# ESPNTPServer.net
KiCad netlist of a schematic drawn in EAGLE
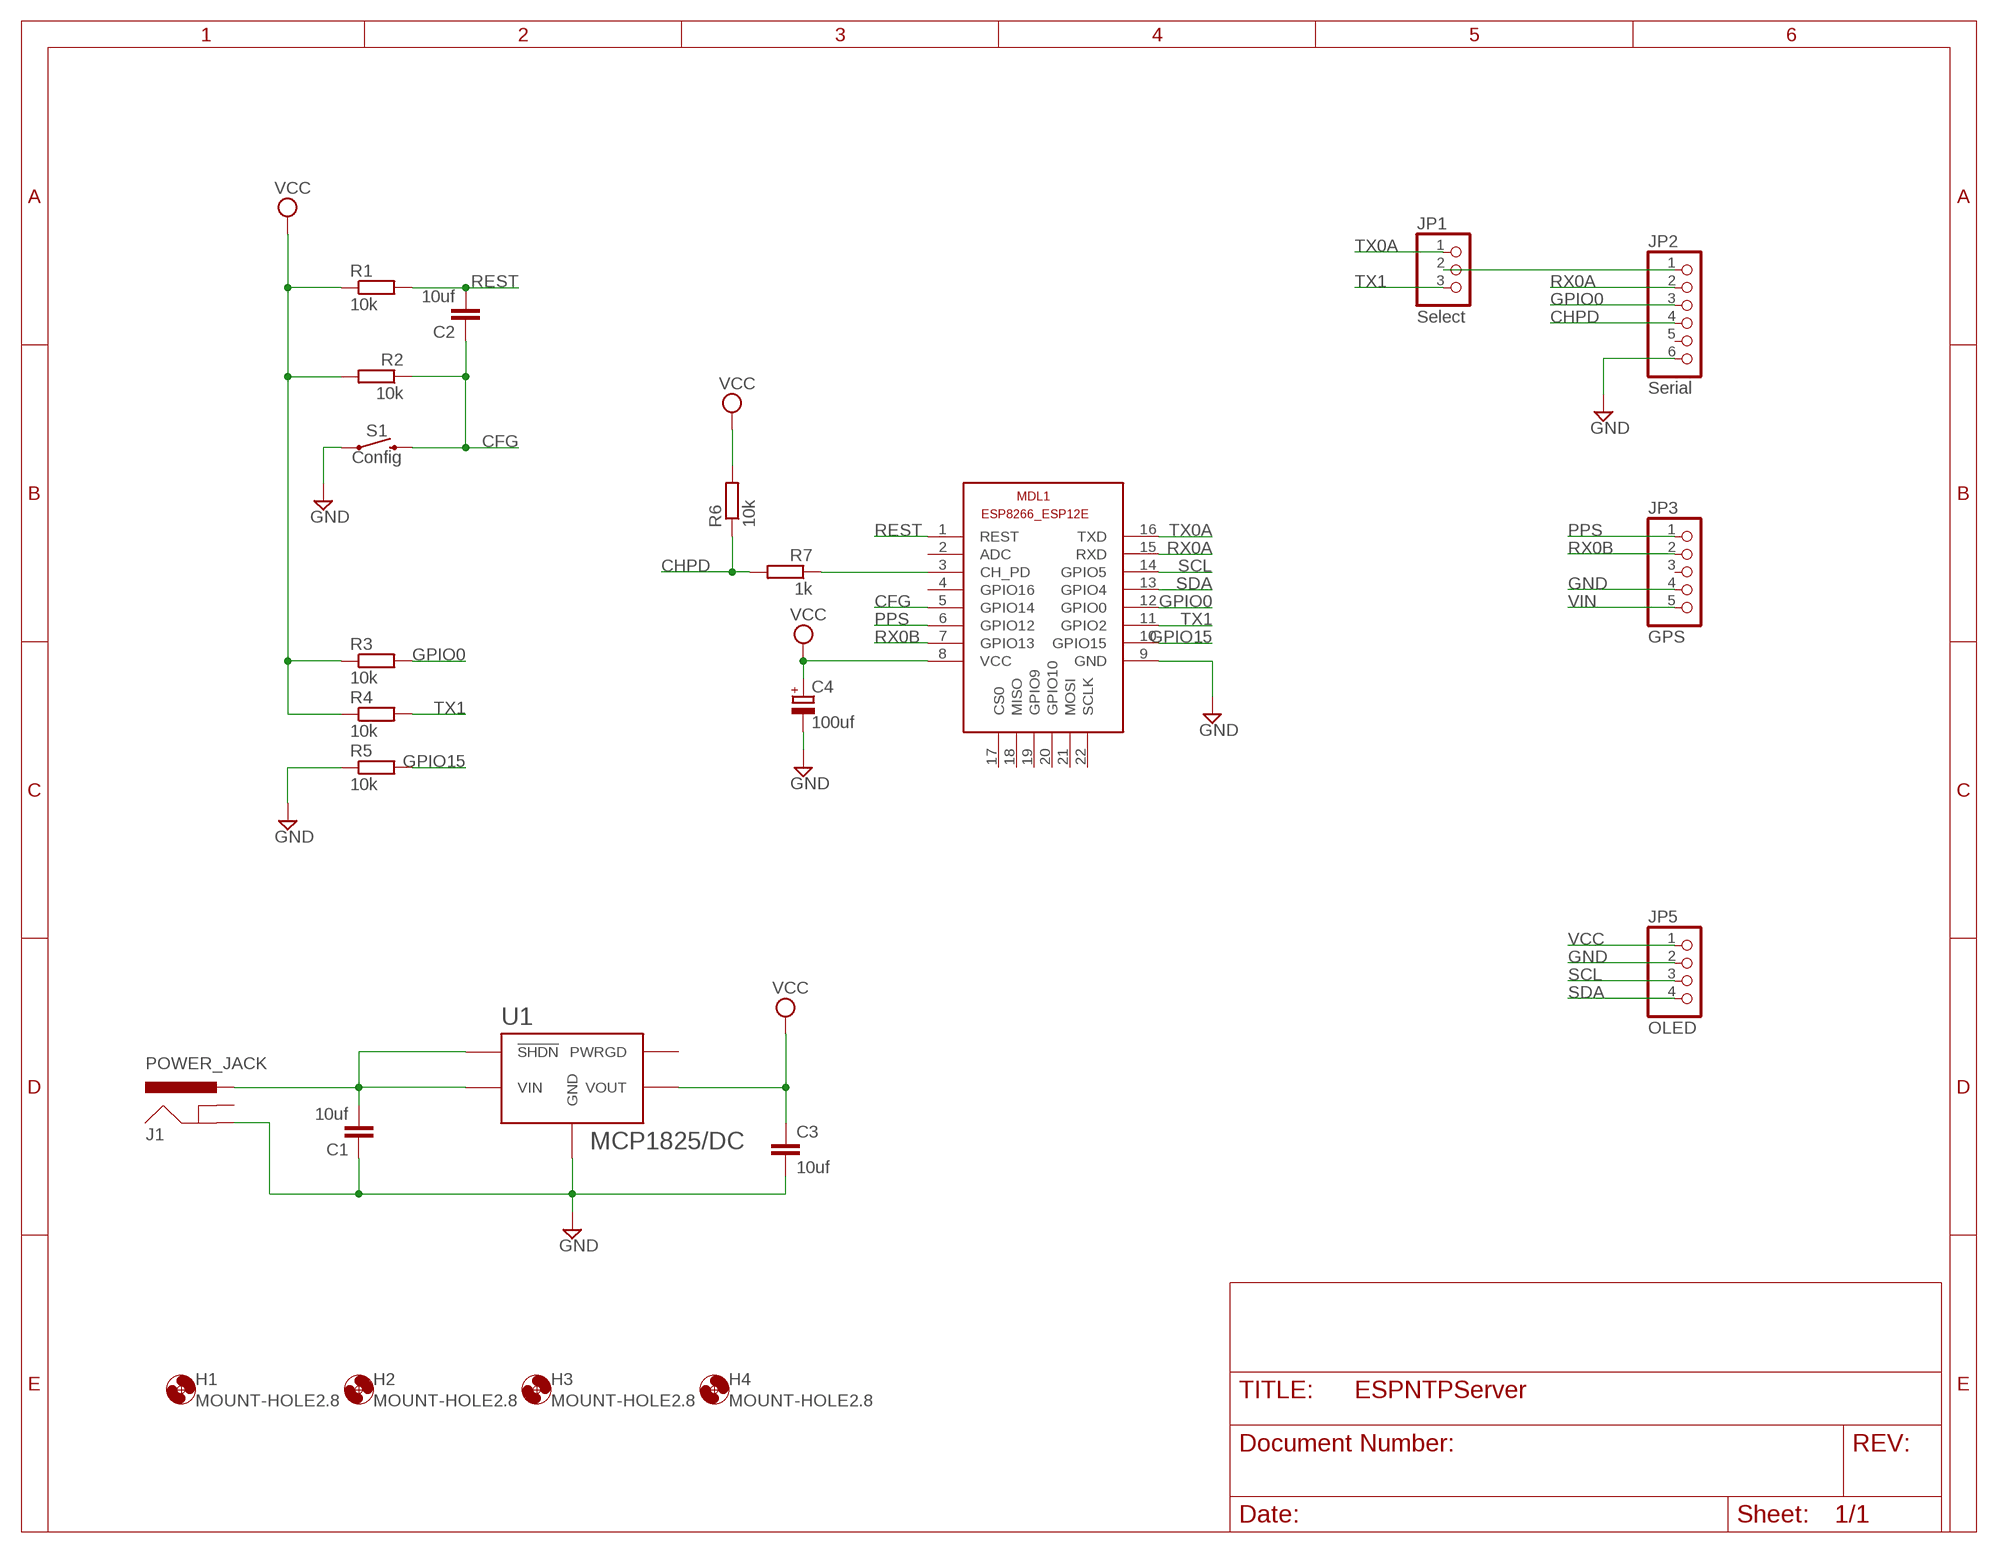
[diagram p0: schematic, sheet 1]

(export (version "E")
  (design (tool "Eeschema 10.0.6"))
  (components
    (comp (ref "C1")
      (value "10uf")
      (footprint "eagle-import:C050-025X075")
      (libsource (lib "eagle-import") (part "C-EU050-025X075"))
    )
    (comp (ref "C2")
      (value "10uf")
      (footprint "eagle-import:C050-025X075")
      (libsource (lib "eagle-import") (part "C-EU050-025X075"))
    )
    (comp (ref "C3")
      (value "10uf")
      (footprint "eagle-import:C050-025X075")
      (libsource (lib "eagle-import") (part "C-EU050-025X075"))
    )
    (comp (ref "C4")
      (value "100uf")
      (footprint "eagle-import:E2,5-5")
      (libsource (lib "eagle-import") (part "CPOL-EUE2.5-5"))
    )
    (comp (ref "H1")
      (value "MOUNT-HOLE2.8")
      (footprint "eagle-import:2,8")
      (libsource (lib "eagle-import") (part "MOUNT-HOLE2.8"))
    )
    (comp (ref "H2")
      (value "MOUNT-HOLE2.8")
      (footprint "eagle-import:2,8")
      (libsource (lib "eagle-import") (part "MOUNT-HOLE2.8"))
    )
    (comp (ref "H3")
      (value "MOUNT-HOLE2.8")
      (footprint "eagle-import:2,8")
      (libsource (lib "eagle-import") (part "MOUNT-HOLE2.8"))
    )
    (comp (ref "H4")
      (value "MOUNT-HOLE2.8")
      (footprint "eagle-import:2,8")
      (libsource (lib "eagle-import") (part "MOUNT-HOLE2.8"))
    )
    (comp (ref "J1")
      (value "POWER_JACK")
      (footprint "eagle-import:POWER_JACK_PTH")
      (libsource (lib "eagle-import") (part "POWER_JACK"))
    )
    (comp (ref "JP1")
      (value "Select")
      (footprint "eagle-import:1X03")
      (libsource (lib "eagle-import") (part "PINHD-1X3"))
    )
    (comp (ref "JP2")
      (value "Serial")
      (footprint "eagle-import:1X06")
      (libsource (lib "eagle-import") (part "PINHD-1X6"))
    )
    (comp (ref "JP3")
      (value "GPS")
      (footprint "eagle-import:1X05")
      (libsource (lib "eagle-import") (part "PINHD-1X5"))
    )
    (comp (ref "JP5")
      (value "OLED")
      (footprint "eagle-import:1X04")
      (libsource (lib "eagle-import") (part "PINHD-1X4"))
    )
    (comp (ref "MDL1")
      (value "ESP8266-12F")
      (footprint "eagle-import:ESP8266-ESP12E")
      (libsource (lib "eagle-import") (part "ESP8266-12EESP8266-ESP12E"))
    )
    (comp (ref "R1")
      (value "10k")
      (footprint "eagle-import:0204V")
      (libsource (lib "eagle-import") (part "R-EU_0204/2V"))
    )
    (comp (ref "R2")
      (value "10k")
      (footprint "eagle-import:0204V")
      (libsource (lib "eagle-import") (part "R-EU_0204/2V"))
    )
    (comp (ref "R3")
      (value "10k")
      (footprint "eagle-import:0204V")
      (libsource (lib "eagle-import") (part "R-EU_0204/2V"))
    )
    (comp (ref "R4")
      (value "10k")
      (footprint "eagle-import:0204V")
      (libsource (lib "eagle-import") (part "R-EU_0204/2V"))
    )
    (comp (ref "R5")
      (value "10k")
      (footprint "eagle-import:0204V")
      (libsource (lib "eagle-import") (part "R-EU_0204/2V"))
    )
    (comp (ref "R6")
      (value "10k")
      (footprint "eagle-import:0204V")
      (libsource (lib "eagle-import") (part "R-EU_0204/2V"))
    )
    (comp (ref "R7")
      (value "1k")
      (footprint "eagle-import:0204V")
      (libsource (lib "eagle-import") (part "R-EU_0204/2V"))
    )
    (comp (ref "S1")
      (value "Config")
      (footprint "eagle-import:TACTILE_SWITCH_PTH_6.0MM")
      (libsource (lib "eagle-import") (part "MOMENTARY-SWITCH-SPST-PTH-6.0MM"))
    )
    (comp (ref "U1")
      (value "MCP1825/DC")
      (footprint "eagle-import:SOT-223-5")
      (libsource (lib "eagle-import") (part "MCP1825/DC"))
    )
  )
  (nets
    (net (code "1") (name "/CFG") (class "Default")
      (node (ref "C2") (pin "1") (pinfunction "1_1") (pintype "passive"))
      (node (ref "MDL1") (pin "5") (pinfunction "GPIO14_5") (pintype "bidirectional"))
      (node (ref "R2") (pin "1") (pinfunction "1_1") (pintype "passive"))
      (node (ref "S1") (pin "3") (pinfunction "2_3") (pintype "passive"))
    )
    (net (code "2") (name "/CHPD") (class "Default")
      (node (ref "JP2") (pin "4") (pinfunction "4_4") (pintype "passive"))
      (node (ref "R6") (pin "1") (pinfunction "1_1") (pintype "passive"))
      (node (ref "R7") (pin "2") (pinfunction "2_2") (pintype "passive"))
    )
    (net (code "3") (name "/GPIO0") (class "Default")
      (node (ref "JP2") (pin "3") (pinfunction "3_3") (pintype "passive"))
      (node (ref "MDL1") (pin "12") (pinfunction "GPIO0_12") (pintype "bidirectional"))
      (node (ref "R3") (pin "2") (pinfunction "2_2") (pintype "passive"))
    )
    (net (code "4") (name "/GPIO15") (class "Default")
      (node (ref "MDL1") (pin "10") (pinfunction "GPIO15_10") (pintype "bidirectional"))
      (node (ref "R5") (pin "2") (pinfunction "2_2") (pintype "passive"))
    )
    (net (code "5") (name "/PPS") (class "Default")
      (node (ref "JP3") (pin "1") (pinfunction "1_1") (pintype "passive"))
      (node (ref "MDL1") (pin "6") (pinfunction "GPIO12_6") (pintype "bidirectional"))
    )
    (net (code "6") (name "/REST") (class "Default")
      (node (ref "C2") (pin "2") (pinfunction "2_2") (pintype "passive"))
      (node (ref "MDL1") (pin "1") (pinfunction "REST_1") (pintype "bidirectional"))
      (node (ref "R1") (pin "2") (pinfunction "2_2") (pintype "passive"))
    )
    (net (code "7") (name "/RX0A") (class "Default")
      (node (ref "JP2") (pin "2") (pinfunction "2_2") (pintype "passive"))
      (node (ref "MDL1") (pin "15") (pinfunction "RXD_15") (pintype "bidirectional"))
    )
    (net (code "8") (name "/RX0B") (class "Default")
      (node (ref "JP3") (pin "2") (pinfunction "2_2") (pintype "passive"))
      (node (ref "MDL1") (pin "7") (pinfunction "GPIO13_7") (pintype "bidirectional"))
    )
    (net (code "9") (name "/SCL") (class "Default")
      (node (ref "JP5") (pin "3") (pinfunction "3_3") (pintype "passive"))
      (node (ref "MDL1") (pin "14") (pinfunction "GPIO5_14") (pintype "bidirectional"))
    )
    (net (code "10") (name "/SDA") (class "Default")
      (node (ref "JP5") (pin "4") (pinfunction "4_4") (pintype "passive"))
      (node (ref "MDL1") (pin "13") (pinfunction "GPIO4_13") (pintype "bidirectional"))
    )
    (net (code "11") (name "/TX0A") (class "Default")
      (node (ref "JP1") (pin "1") (pinfunction "1_1") (pintype "passive"))
      (node (ref "MDL1") (pin "16") (pinfunction "TXD_16") (pintype "bidirectional"))
    )
    (net (code "12") (name "/TX1") (class "Default")
      (node (ref "JP1") (pin "3") (pinfunction "3_3") (pintype "passive"))
      (node (ref "MDL1") (pin "11") (pinfunction "GPIO2_11") (pintype "bidirectional"))
      (node (ref "R4") (pin "2") (pinfunction "2_2") (pintype "passive"))
    )
    (net (code "13") (name "/VIN") (class "Default")
      (node (ref "C1") (pin "2") (pinfunction "2_2") (pintype "passive"))
      (node (ref "J1") (pin "PWR") (pinfunction "PWR_PWR") (pintype "bidirectional"))
      (node (ref "JP3") (pin "5") (pinfunction "5_5") (pintype "passive"))
      (node (ref "U1") (pin "P$1") (pinfunction "~{SHDN}_P$1") (pintype "input"))
      (node (ref "U1") (pin "P$2") (pinfunction "VIN_P$2") (pintype "power_in"))
    )
    (net (code "14") (name "GND") (class "Default")
      (node (ref "C1") (pin "1") (pinfunction "1_1") (pintype "passive"))
      (node (ref "C3") (pin "2") (pinfunction "2_2") (pintype "passive"))
      (node (ref "C4") (pin "-") (pinfunction "-_-") (pintype "passive"))
      (node (ref "J1") (pin "GND") (pinfunction "GND_GND") (pintype "bidirectional"))
      (node (ref "JP2") (pin "6") (pinfunction "6_6") (pintype "passive"))
      (node (ref "JP3") (pin "4") (pinfunction "4_4") (pintype "passive"))
      (node (ref "JP5") (pin "2") (pinfunction "2_2") (pintype "passive"))
      (node (ref "MDL1") (pin "9") (pinfunction "GND_9") (pintype "bidirectional"))
      (node (ref "R5") (pin "1") (pinfunction "1_1") (pintype "passive"))
      (node (ref "S1") (pin "1") (pinfunction "1_1") (pintype "passive"))
      (node (ref "U1") (pin "P$3") (pinfunction "GND_P$3") (pintype "power_in"))
      (node (ref "U1") (pin "P$6") (pinfunction "GND_P$6") (pintype "power_in"))
    )
    (net (code "15") (name "Net-(JP1-Pad2)") (class "Default")
      (node (ref "JP1") (pin "2") (pinfunction "2_2") (pintype "passive"))
      (node (ref "JP2") (pin "1") (pinfunction "1_1") (pintype "passive"))
    )
    (net (code "16") (name "Net-(MDL1-CH_PD)") (class "Default")
      (node (ref "MDL1") (pin "3") (pinfunction "CH_PD_3") (pintype "bidirectional"))
      (node (ref "R7") (pin "1") (pinfunction "1_1") (pintype "passive"))
    )
    (net (code "17") (name "VCC") (class "Default")
      (node (ref "C3") (pin "1") (pinfunction "1_1") (pintype "passive"))
      (node (ref "C4") (pin "+") (pinfunction "+_+") (pintype "passive"))
      (node (ref "JP5") (pin "1") (pinfunction "1_1") (pintype "passive"))
      (node (ref "MDL1") (pin "8") (pinfunction "VCC_8") (pintype "bidirectional"))
      (node (ref "R1") (pin "1") (pinfunction "1_1") (pintype "passive"))
      (node (ref "R2") (pin "2") (pinfunction "2_2") (pintype "passive"))
      (node (ref "R3") (pin "1") (pinfunction "1_1") (pintype "passive"))
      (node (ref "R4") (pin "1") (pinfunction "1_1") (pintype "passive"))
      (node (ref "R6") (pin "2") (pinfunction "2_2") (pintype "passive"))
      (node (ref "U1") (pin "P$4") (pinfunction "VOUT_P$4") (pintype "power_in"))
    )
    (net (code "18") (name "unconnected-(J1-PadGNDBREAK)") (class "Default")
      (node (ref "J1") (pin "GNDBREAK") (pinfunction "GNDBREAK_GNDBREAK") (pintype "bidirectional"))
    )
    (net (code "19") (name "unconnected-(JP2-Pad5)") (class "Default")
      (node (ref "JP2") (pin "5") (pinfunction "5_5") (pintype "passive"))
    )
    (net (code "20") (name "unconnected-(JP3-Pad3)") (class "Default")
      (node (ref "JP3") (pin "3") (pinfunction "3_3") (pintype "passive"))
    )
    (net (code "21") (name "unconnected-(MDL1-ADC-Pad2)") (class "Default")
      (node (ref "MDL1") (pin "2") (pinfunction "ADC_2") (pintype "bidirectional"))
    )
    (net (code "22") (name "unconnected-(MDL1-CS0-Pad17)") (class "Default")
      (node (ref "MDL1") (pin "17") (pinfunction "CS0_17") (pintype "bidirectional"))
    )
    (net (code "23") (name "unconnected-(MDL1-GPIO9-Pad19)") (class "Default")
      (node (ref "MDL1") (pin "19") (pinfunction "GPIO9_19") (pintype "bidirectional"))
    )
    (net (code "24") (name "unconnected-(MDL1-GPIO10-Pad20)") (class "Default")
      (node (ref "MDL1") (pin "20") (pinfunction "GPIO10_20") (pintype "bidirectional"))
    )
    (net (code "25") (name "unconnected-(MDL1-GPIO16-Pad4)") (class "Default")
      (node (ref "MDL1") (pin "4") (pinfunction "GPIO16_4") (pintype "bidirectional"))
    )
    (net (code "26") (name "unconnected-(MDL1-MISO-Pad18)") (class "Default")
      (node (ref "MDL1") (pin "18") (pinfunction "MISO_18") (pintype "bidirectional"))
    )
    (net (code "27") (name "unconnected-(MDL1-MOSI-Pad21)") (class "Default")
      (node (ref "MDL1") (pin "21") (pinfunction "MOSI_21") (pintype "bidirectional"))
    )
    (net (code "28") (name "unconnected-(MDL1-SCLK-Pad22)") (class "Default")
      (node (ref "MDL1") (pin "22") (pinfunction "SCLK_22") (pintype "bidirectional"))
    )
    (net (code "29") (name "unconnected-(U1-PWRGD-PadP$5)") (class "Default")
      (node (ref "U1") (pin "P$5") (pinfunction "PWRGD_P$5") (pintype "output"))
    )
  )
)
